# I2C-to-SPI.net
KiCad netlist of a schematic drawn in Altium Designer
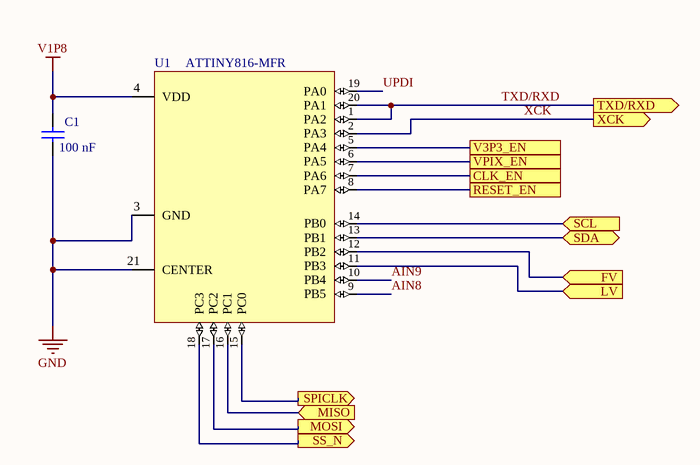
[diagram p0: I2C-to-SPI.SchDoc]

(export (version "E")
  (design (tool "Eeschema 10.0.6"))
  (components
    (comp (ref "C1")
      (value "GRM033C71C104KE14D")
      (footprint "PCB-v6eq6etc9p7u7qdkgnno-1")
      (description "0.1 µF ±10% 16V Ceramic Capacitor X7S 0201 (0603 Metric)")
      (fields (field (name "CAPACITANCE") "100 nF"))
      (libsource (lib "Python_Imaging_1") (part "CMP-cc290632c88a13ee-3"))
    )
    (comp (ref "U1")
      (value "ATTINY816-MFR")
      (footprint "PCB-hv4cq49t2e9uf1npj5by-1")
      (description "AVR series Microcontroller IC 8-Bit 16MHz 8KB (8K x 8) FLASH 20-VQFN (3x3)")
      (libsource (lib "Python_Imaging_1") (part "SYM-1cb5d12d1e47c372-1"))
    )
  )
  (nets
    (net (code "1") (name "/AIN8") (class "Default")
      (node (ref "U1") (pin "9") (pinfunction "PB5_9") (pintype "bidirectional"))
    )
    (net (code "2") (name "/AIN9") (class "Default")
      (node (ref "U1") (pin "10") (pinfunction "PB4_10") (pintype "bidirectional"))
    )
    (net (code "3") (name "/CLK_EN") (class "Default")
      (node (ref "U1") (pin "7") (pinfunction "PA6_7") (pintype "bidirectional"))
    )
    (net (code "4") (name "/FV") (class "Default")
      (node (ref "U1") (pin "12") (pinfunction "PB2_12") (pintype "bidirectional"))
    )
    (net (code "5") (name "/LV") (class "Default")
      (node (ref "U1") (pin "11") (pinfunction "PB3_11") (pintype "bidirectional"))
    )
    (net (code "6") (name "/MISO") (class "Default")
      (node (ref "U1") (pin "16") (pinfunction "PC1_16") (pintype "bidirectional"))
    )
    (net (code "7") (name "/MOSI") (class "Default")
      (node (ref "U1") (pin "17") (pinfunction "PC2_17") (pintype "bidirectional"))
    )
    (net (code "8") (name "/RESET_EN") (class "Default")
      (node (ref "U1") (pin "8") (pinfunction "PA7_8") (pintype "bidirectional"))
    )
    (net (code "9") (name "/SCL") (class "Default")
      (node (ref "U1") (pin "14") (pinfunction "PB0_14") (pintype "bidirectional"))
    )
    (net (code "10") (name "/SDA") (class "Default")
      (node (ref "U1") (pin "13") (pinfunction "PB1_13") (pintype "bidirectional"))
    )
    (net (code "11") (name "/SPICLK") (class "Default")
      (node (ref "U1") (pin "15") (pinfunction "PC0_15") (pintype "bidirectional"))
    )
    (net (code "12") (name "/SS_N") (class "Default")
      (node (ref "U1") (pin "18") (pinfunction "PC3_18") (pintype "bidirectional"))
    )
    (net (code "13") (name "/TXD{slash}RXD") (class "Default")
      (node (ref "U1") (pin "1") (pinfunction "PA2_1") (pintype "bidirectional"))
      (node (ref "U1") (pin "20") (pinfunction "PA1_20") (pintype "bidirectional"))
    )
    (net (code "14") (name "/UPDI") (class "Default")
      (node (ref "U1") (pin "19") (pinfunction "PA0_19") (pintype "bidirectional"))
    )
    (net (code "15") (name "/V3P3_EN") (class "Default")
      (node (ref "U1") (pin "5") (pinfunction "PA4_5") (pintype "bidirectional"))
    )
    (net (code "16") (name "/VPIX_EN") (class "Default")
      (node (ref "U1") (pin "6") (pinfunction "PA5_6") (pintype "bidirectional"))
    )
    (net (code "17") (name "/XCK") (class "Default")
      (node (ref "U1") (pin "2") (pinfunction "PA3_2") (pintype "bidirectional"))
    )
    (net (code "18") (name "GND") (class "Default")
      (node (ref "C1") (pin "1") (pinfunction "1_1") (pintype "passive"))
      (node (ref "U1") (pin "21") (pinfunction "CENTER_21") (pintype "power_in"))
      (node (ref "U1") (pin "3") (pinfunction "GND_3") (pintype "power_in"))
    )
    (net (code "19") (name "V1P8") (class "Default")
      (node (ref "C1") (pin "2") (pinfunction "2_2") (pintype "passive"))
      (node (ref "U1") (pin "4") (pinfunction "VDD_4") (pintype "power_in"))
    )
  )
)
